# main.net
KiCad netlist of a schematic drawn in Altium Designer
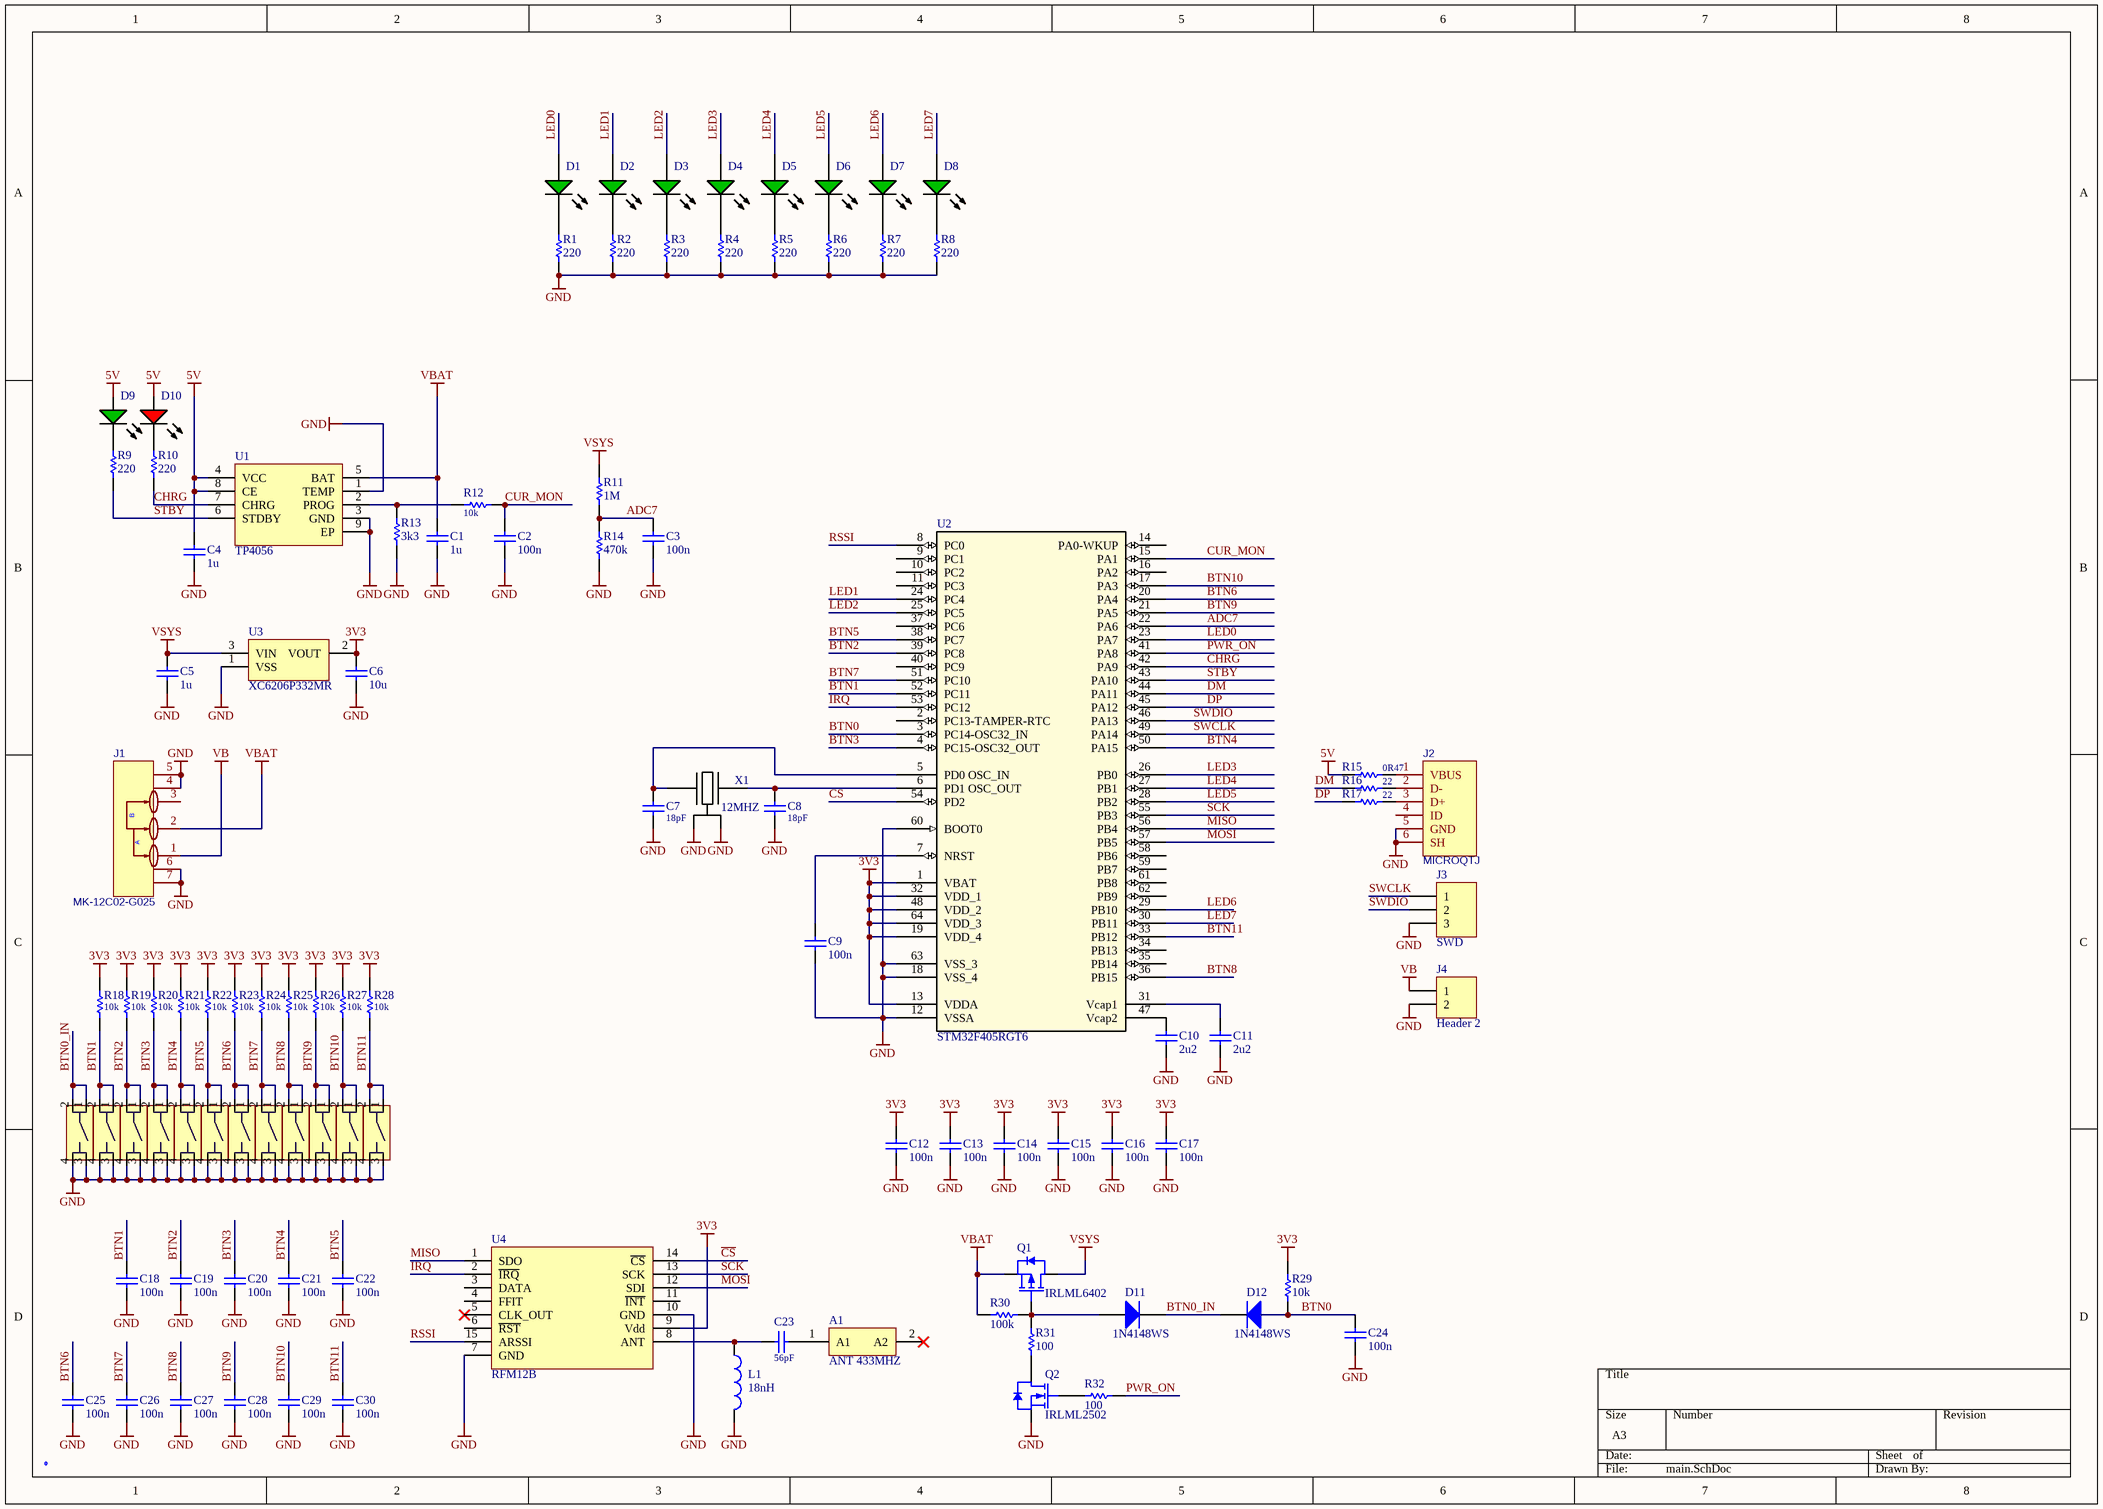
[diagram p0: main.SchDoc]

(export (version "E")
  (design (tool "Eeschema 10.0.6"))
  (components
    (comp (ref "A1")
      (value "ANT 433MHZ")
      (footprint "0433AT62A0020")
      (description "433 MHz ISM Antenna")
      (libsource (lib "Schlib1") (part "Component_2"))
    )
    (comp (ref "C1") (value "1u") (footprint "C1206") (libsource (lib "Miscellaneous Devices") (part "Cap")))
    (comp (ref "C2")
      (value "100n")
      (footprint "C0603")
      (libsource (lib "Miscellaneous Devices") (part "Cap"))
    )
    (comp (ref "C3")
      (value "100n")
      (footprint "C0603")
      (libsource (lib "Miscellaneous Devices") (part "Cap"))
    )
    (comp (ref "C4") (value "1u") (footprint "C1206") (libsource (lib "Miscellaneous Devices") (part "Cap")))
    (comp (ref "C5") (value "1u") (footprint "C1206") (libsource (lib "Miscellaneous Devices") (part "Cap")))
    (comp (ref "C6") (value "10u") (footprint "C1206") (libsource (lib "Miscellaneous Devices") (part "Cap")))
    (comp (ref "C7")
      (value "18pF")
      (footprint "C0402")
      (description "18pF 0402")
      (libsource (lib "Miscellaneous Devices") (part "CAP"))
    )
    (comp (ref "C8")
      (value "18pF")
      (footprint "C0402")
      (description "18pF 0402")
      (libsource (lib "Miscellaneous Devices") (part "CAP"))
    )
    (comp (ref "C9")
      (value "100n")
      (footprint "C0402")
      (libsource (lib "Miscellaneous Devices") (part "Cap"))
    )
    (comp (ref "C10")
      (value "2u2")
      (footprint "C0603")
      (libsource (lib "Miscellaneous Devices") (part "Cap"))
    )
    (comp (ref "C11")
      (value "2u2")
      (footprint "C0603")
      (libsource (lib "Miscellaneous Devices") (part "Cap"))
    )
    (comp (ref "C12")
      (value "100n")
      (footprint "C0402")
      (libsource (lib "Miscellaneous Devices") (part "Cap"))
    )
    (comp (ref "C13")
      (value "100n")
      (footprint "C0402")
      (libsource (lib "Miscellaneous Devices") (part "Cap"))
    )
    (comp (ref "C14")
      (value "100n")
      (footprint "C0402")
      (libsource (lib "Miscellaneous Devices") (part "Cap"))
    )
    (comp (ref "C15")
      (value "100n")
      (footprint "C0402")
      (libsource (lib "Miscellaneous Devices") (part "Cap"))
    )
    (comp (ref "C16")
      (value "100n")
      (footprint "C0402")
      (libsource (lib "Miscellaneous Devices") (part "Cap"))
    )
    (comp (ref "C17")
      (value "100n")
      (footprint "C0402")
      (libsource (lib "Miscellaneous Devices") (part "Cap"))
    )
    (comp (ref "C18")
      (value "100n")
      (footprint "C0402")
      (libsource (lib "Miscellaneous Devices") (part "Cap"))
    )
    (comp (ref "C19")
      (value "100n")
      (footprint "C0402")
      (libsource (lib "Miscellaneous Devices") (part "Cap"))
    )
    (comp (ref "C20")
      (value "100n")
      (footprint "C0402")
      (libsource (lib "Miscellaneous Devices") (part "Cap"))
    )
    (comp (ref "C21")
      (value "100n")
      (footprint "C0402")
      (libsource (lib "Miscellaneous Devices") (part "Cap"))
    )
    (comp (ref "C22")
      (value "100n")
      (footprint "C0402")
      (libsource (lib "Miscellaneous Devices") (part "Cap"))
    )
    (comp (ref "C23")
      (value "56pF")
      (footprint "C0402")
      (libsource (lib "Miscellaneous Devices") (part "CAP"))
    )
    (comp (ref "C24")
      (value "100n")
      (footprint "C0402")
      (libsource (lib "Miscellaneous Devices") (part "Cap"))
    )
    (comp (ref "C25")
      (value "100n")
      (footprint "C0402")
      (libsource (lib "Miscellaneous Devices") (part "Cap"))
    )
    (comp (ref "C26")
      (value "100n")
      (footprint "C0402")
      (libsource (lib "Miscellaneous Devices") (part "Cap"))
    )
    (comp (ref "C27")
      (value "100n")
      (footprint "C0402")
      (libsource (lib "Miscellaneous Devices") (part "Cap"))
    )
    (comp (ref "C28")
      (value "100n")
      (footprint "C0402")
      (libsource (lib "Miscellaneous Devices") (part "Cap"))
    )
    (comp (ref "C29")
      (value "100n")
      (footprint "C0402")
      (libsource (lib "Miscellaneous Devices") (part "Cap"))
    )
    (comp (ref "C30")
      (value "100n")
      (footprint "C0402")
      (libsource (lib "Miscellaneous Devices") (part "Cap"))
    )
    (comp (ref "D1")
      (value "GRN")
      (footprint "LED-0603-GRN")
      (description "LED 0603 GRN")
      (libsource (lib "Miscellaneous Devices") (part "LED-0603-GREEN"))
    )
    (comp (ref "D2")
      (value "GRN")
      (footprint "LED-0603-GRN")
      (description "LED 0603 GRN")
      (libsource (lib "Miscellaneous Devices") (part "LED-0603-GREEN"))
    )
    (comp (ref "D3")
      (value "GRN")
      (footprint "LED-0603-GRN")
      (description "LED 0603 GRN")
      (libsource (lib "Miscellaneous Devices") (part "LED-0603-GREEN"))
    )
    (comp (ref "D4")
      (value "GRN")
      (footprint "LED-0603-GRN")
      (description "LED 0603 GRN")
      (libsource (lib "Miscellaneous Devices") (part "LED-0603-GREEN"))
    )
    (comp (ref "D5")
      (value "GRN")
      (footprint "LED-0603-GRN")
      (description "LED 0603 GRN")
      (libsource (lib "Miscellaneous Devices") (part "LED-0603-GREEN"))
    )
    (comp (ref "D6")
      (value "GRN")
      (footprint "LED-0603-GRN")
      (description "LED 0603 GRN")
      (libsource (lib "Miscellaneous Devices") (part "LED-0603-GREEN"))
    )
    (comp (ref "D7")
      (value "GRN")
      (footprint "LED-0603-GRN")
      (description "LED 0603 GRN")
      (libsource (lib "Miscellaneous Devices") (part "LED-0603-GREEN"))
    )
    (comp (ref "D8")
      (value "GRN")
      (footprint "LED-0603-GRN")
      (description "LED 0603 GRN")
      (libsource (lib "Miscellaneous Devices") (part "LED-0603-GREEN"))
    )
    (comp (ref "D9")
      (value "GRN")
      (footprint "LED-0603-GRN")
      (description "LED 0603 GRN")
      (libsource (lib "") (part "LED-0603-GREEN_1"))
    )
    (comp (ref "D10")
      (value "RED")
      (footprint "LED-0603-RED")
      (description "LED 0603 RED")
      (libsource (lib "Miscellaneous Devices") (part "LED-0603-RED"))
    )
    (comp (ref "D11")
      (value "1N4148WS")
      (footprint "SOD-323")
      (libsource (lib "Miscellaneous Devices") (part "US1M-13-F"))
    )
    (comp (ref "D12")
      (value "1N4148WS")
      (footprint "SOD-323")
      (libsource (lib "Miscellaneous Devices") (part "US1M-13-F"))
    )
    (comp (ref "J1")
      (value "MK-12C02-G025")
      (footprint "SW-SMD_MK-12C02-G025")
      (fields (field (name "LCSC PART NUMBER") "C778186"))
      (libsource (lib "Schlib1") (part "MK-12C02-G025"))
    )
    (comp (ref "J2")
      (value "MICROQTJ")
      (footprint "CONN-USB-MICRO_#1")
      (libsource (lib "Schlib2") (part "MICROQTJ"))
    )
    (comp (ref "J3")
      (value "SWD")
      (footprint "HDR-1X3_2.54")
      (libsource (lib "Miscellaneous Devices") (part "Header 3"))
    )
    (comp (ref "J4")
      (value "Header 2")
      (footprint "HDR-1X2_2.54")
      (libsource (lib "Schlib1") (part "Header 2"))
    )
    (comp (ref "L1")
      (value "18nH")
      (footprint "L0402")
      (libsource (lib "Miscellaneous Devices") (part "BLM18AG601SN1D"))
    )
    (comp (ref "LOGO1") (value "LOGO") (footprint "LOGO") (libsource (lib "Schlib1") (part "LOGO")))
    (comp (ref "Q1") (value "IRLML6402") (footprint "SOT-23") (libsource (lib "") (part "2N7002_1")))
    (comp (ref "Q2")
      (value "IRLML2502")
      (footprint "SOT-23")
      (libsource (lib "Miscellaneous Devices") (part "2N7002"))
    )
    (comp (ref "R1")
      (value "220")
      (footprint "R0603")
      (libsource (lib "Miscellaneous Devices") (part "Res1"))
    )
    (comp (ref "R2")
      (value "220")
      (footprint "R0603")
      (libsource (lib "Miscellaneous Devices") (part "Res1"))
    )
    (comp (ref "R3")
      (value "220")
      (footprint "R0603")
      (libsource (lib "Miscellaneous Devices") (part "Res1"))
    )
    (comp (ref "R4")
      (value "220")
      (footprint "R0603")
      (libsource (lib "Miscellaneous Devices") (part "Res1"))
    )
    (comp (ref "R5")
      (value "220")
      (footprint "R0603")
      (libsource (lib "Miscellaneous Devices") (part "Res1"))
    )
    (comp (ref "R6")
      (value "220")
      (footprint "R0603")
      (libsource (lib "Miscellaneous Devices") (part "Res1"))
    )
    (comp (ref "R7")
      (value "220")
      (footprint "R0603")
      (libsource (lib "Miscellaneous Devices") (part "Res1"))
    )
    (comp (ref "R8")
      (value "220")
      (footprint "R0603")
      (libsource (lib "Miscellaneous Devices") (part "Res1"))
    )
    (comp (ref "R9")
      (value "220")
      (footprint "R0603")
      (libsource (lib "Miscellaneous Devices") (part "Res1"))
    )
    (comp (ref "R10")
      (value "220")
      (footprint "R0603")
      (libsource (lib "Miscellaneous Devices") (part "Res1"))
    )
    (comp (ref "R11")
      (value "1M")
      (footprint "R0603")
      (libsource (lib "Miscellaneous Devices") (part "Res1"))
    )
    (comp (ref "R12")
      (value "10k")
      (footprint "R0603")
      (libsource (lib "Miscellaneous Devices") (part "RES"))
    )
    (comp (ref "R13")
      (value "3k3")
      (footprint "R0603")
      (libsource (lib "Miscellaneous Devices") (part "Res1"))
    )
    (comp (ref "R14")
      (value "470k")
      (footprint "R0603")
      (libsource (lib "Miscellaneous Devices") (part "Res1"))
    )
    (comp (ref "R15")
      (value "0R47")
      (footprint "R0603")
      (libsource (lib "Miscellaneous Devices") (part "RES"))
    )
    (comp (ref "R16") (value "22") (footprint "R0603") (libsource (lib "Miscellaneous Devices") (part "RES")))
    (comp (ref "R17") (value "22") (footprint "R0603") (libsource (lib "Miscellaneous Devices") (part "RES")))
    (comp (ref "R18")
      (value "10k")
      (footprint "R0603")
      (libsource (lib "Miscellaneous Devices") (part "RES"))
    )
    (comp (ref "R19")
      (value "10k")
      (footprint "R0603")
      (libsource (lib "Miscellaneous Devices") (part "RES"))
    )
    (comp (ref "R20")
      (value "10k")
      (footprint "R0603")
      (libsource (lib "Miscellaneous Devices") (part "RES"))
    )
    (comp (ref "R21")
      (value "10k")
      (footprint "R0603")
      (libsource (lib "Miscellaneous Devices") (part "RES"))
    )
    (comp (ref "R22")
      (value "10k")
      (footprint "R0603")
      (libsource (lib "Miscellaneous Devices") (part "RES"))
    )
    (comp (ref "R23")
      (value "10k")
      (footprint "R0603")
      (libsource (lib "Miscellaneous Devices") (part "RES"))
    )
    (comp (ref "R24")
      (value "10k")
      (footprint "R0603")
      (libsource (lib "Miscellaneous Devices") (part "RES"))
    )
    (comp (ref "R25")
      (value "10k")
      (footprint "R0603")
      (libsource (lib "Miscellaneous Devices") (part "RES"))
    )
    (comp (ref "R26")
      (value "10k")
      (footprint "R0603")
      (libsource (lib "Miscellaneous Devices") (part "RES"))
    )
    (comp (ref "R27")
      (value "10k")
      (footprint "R0603")
      (libsource (lib "Miscellaneous Devices") (part "RES"))
    )
    (comp (ref "R28")
      (value "10k")
      (footprint "R0603")
      (libsource (lib "Miscellaneous Devices") (part "RES"))
    )
    (comp (ref "R29")
      (value "10k")
      (footprint "R0603")
      (libsource (lib "Miscellaneous Devices") (part "Res1"))
    )
    (comp (ref "R30")
      (value "100k")
      (footprint "R0603")
      (libsource (lib "Miscellaneous Devices") (part "Res1"))
    )
    (comp (ref "R31")
      (value "100")
      (footprint "R0603")
      (libsource (lib "Miscellaneous Devices") (part "Res1"))
    )
    (comp (ref "R32")
      (value "100")
      (footprint "R0603")
      (libsource (lib "Miscellaneous Devices") (part "Res1"))
    )
    (comp (ref "SW1")
      (value "PTS810SJS250")
      (footprint "BTN_PTS810")
      (libsource (lib "Miscellaneous Devices") (part "Component_1"))
    )
    (comp (ref "SW2")
      (value "PTS810SJS250")
      (footprint "BTN_PTS810")
      (libsource (lib "Miscellaneous Devices") (part "Component_1"))
    )
    (comp (ref "SW3")
      (value "PTS810SJS250")
      (footprint "BTN_PTS810")
      (libsource (lib "Miscellaneous Devices") (part "Component_1"))
    )
    (comp (ref "SW4")
      (value "PTS810SJS250")
      (footprint "BTN_PTS810")
      (libsource (lib "Miscellaneous Devices") (part "Component_1"))
    )
    (comp (ref "SW5")
      (value "PTS810SJS250")
      (footprint "BTN_PTS810")
      (libsource (lib "Miscellaneous Devices") (part "Component_1"))
    )
    (comp (ref "SW6")
      (value "PTS810SJS250")
      (footprint "BTN_PTS810")
      (libsource (lib "Miscellaneous Devices") (part "Component_1"))
    )
    (comp (ref "SW7")
      (value "PTS810SJS250")
      (footprint "BTN_PTS810")
      (libsource (lib "Miscellaneous Devices") (part "Component_1"))
    )
    (comp (ref "SW8")
      (value "PTS810SJS250")
      (footprint "BTN_PTS810")
      (libsource (lib "Miscellaneous Devices") (part "Component_1"))
    )
    (comp (ref "SW9")
      (value "PTS810SJS250")
      (footprint "BTN_PTS810")
      (libsource (lib "Miscellaneous Devices") (part "Component_1"))
    )
    (comp (ref "SW10")
      (value "PTS810SJS250")
      (footprint "BTN_PTS810")
      (libsource (lib "Miscellaneous Devices") (part "Component_1"))
    )
    (comp (ref "SW11")
      (value "PTS810SJS250")
      (footprint "BTN_PTS810")
      (libsource (lib "Miscellaneous Devices") (part "Component_1"))
    )
    (comp (ref "SW12")
      (value "PTS810SJS250")
      (footprint "BTN_PTS810")
      (libsource (lib "Miscellaneous Devices") (part "Component_1"))
    )
    (comp (ref "U1") (value "TP4056") (footprint "PowerSOIC-8") (libsource (lib "Schlib1") (part "TP4056")))
    (comp (ref "U2")
      (value "STM32F405RGT6")
      (footprint "LQFP-64")
      (description "MCU STM32F405RGT6")
      (libsource (lib "RozumLibrary") (part "STM32F405RGT6"))
    )
    (comp (ref "U3")
      (value "XC6206P332MR")
      (footprint "SOT-23")
      (libsource (lib "Schlib1") (part "Component_4_1"))
    )
    (comp (ref "U4") (value "RFM12B") (footprint "RFM12B") (libsource (lib "Schlib1") (part "Component_1_1")))
    (comp (ref "X1")
      (value "12MHZ")
      (footprint "CRYSTAL_3.2x2.5mm")
      (description "X322512MOB4SI")
      (libsource (lib "Miscellaneous Devices") (part "CRYSTAL 12MHZ 3.20mm x 2.50mm"))
    )
  )
  (nets
    (net (code "1") (name "/ADC7") (class "Default")
      (node (ref "C3") (pin "2") (pinfunction "2_2") (pintype "passive"))
      (node (ref "R11") (pin "1") (pinfunction "1_1") (pintype "passive"))
      (node (ref "R14") (pin "2") (pinfunction "2_2") (pintype "passive"))
      (node (ref "U2") (pin "22") (pinfunction "PA6_22") (pintype "bidirectional"))
    )
    (net (code "2") (name "/BTN0") (class "Default")
      (node (ref "C24") (pin "2") (pinfunction "2_2") (pintype "passive"))
      (node (ref "D12") (pin "1") (pinfunction "A_1") (pintype "passive"))
      (node (ref "R29") (pin "2") (pinfunction "2_2") (pintype "passive"))
      (node (ref "U2") (pin "3") (pinfunction "PC14-OSC32_IN_3") (pintype "bidirectional"))
    )
    (net (code "3") (name "/BTN0_IN") (class "Default")
      (node (ref "D11") (pin "2") (pinfunction "K_2") (pintype "passive"))
      (node (ref "D12") (pin "2") (pinfunction "K_2") (pintype "passive"))
      (node (ref "SW1") (pin "1") (pinfunction "1_1") (pintype "passive"))
      (node (ref "SW1") (pin "2") (pinfunction "2_2") (pintype "passive"))
    )
    (net (code "4") (name "/BTN1") (class "Default")
      (node (ref "C18") (pin "2") (pinfunction "2_2") (pintype "passive"))
      (node (ref "R18") (pin "1") (pinfunction "1_1") (pintype "passive"))
      (node (ref "SW2") (pin "1") (pinfunction "1_1") (pintype "passive"))
      (node (ref "SW2") (pin "2") (pinfunction "2_2") (pintype "passive"))
      (node (ref "U2") (pin "52") (pinfunction "PC11_52") (pintype "bidirectional"))
    )
    (net (code "5") (name "/BTN2") (class "Default")
      (node (ref "C19") (pin "2") (pinfunction "2_2") (pintype "passive"))
      (node (ref "R19") (pin "1") (pinfunction "1_1") (pintype "passive"))
      (node (ref "SW3") (pin "1") (pinfunction "1_1") (pintype "passive"))
      (node (ref "SW3") (pin "2") (pinfunction "2_2") (pintype "passive"))
      (node (ref "U2") (pin "39") (pinfunction "PC8_39") (pintype "bidirectional"))
    )
    (net (code "6") (name "/BTN3") (class "Default")
      (node (ref "C20") (pin "2") (pinfunction "2_2") (pintype "passive"))
      (node (ref "R20") (pin "1") (pinfunction "1_1") (pintype "passive"))
      (node (ref "SW4") (pin "1") (pinfunction "1_1") (pintype "passive"))
      (node (ref "SW4") (pin "2") (pinfunction "2_2") (pintype "passive"))
      (node (ref "U2") (pin "4") (pinfunction "PC15-OSC32_OUT_4") (pintype "bidirectional"))
    )
    (net (code "7") (name "/BTN4") (class "Default")
      (node (ref "C21") (pin "2") (pinfunction "2_2") (pintype "passive"))
      (node (ref "R21") (pin "1") (pinfunction "1_1") (pintype "passive"))
      (node (ref "SW5") (pin "1") (pinfunction "1_1") (pintype "passive"))
      (node (ref "SW5") (pin "2") (pinfunction "2_2") (pintype "passive"))
      (node (ref "U2") (pin "50") (pinfunction "PA15_50") (pintype "bidirectional"))
    )
    (net (code "8") (name "/BTN5") (class "Default")
      (node (ref "C22") (pin "2") (pinfunction "2_2") (pintype "passive"))
      (node (ref "R22") (pin "1") (pinfunction "1_1") (pintype "passive"))
      (node (ref "SW6") (pin "1") (pinfunction "1_1") (pintype "passive"))
      (node (ref "SW6") (pin "2") (pinfunction "2_2") (pintype "passive"))
      (node (ref "U2") (pin "38") (pinfunction "PC7_38") (pintype "bidirectional"))
    )
    (net (code "9") (name "/BTN6") (class "Default")
      (node (ref "C25") (pin "2") (pinfunction "2_2") (pintype "passive"))
      (node (ref "R23") (pin "1") (pinfunction "1_1") (pintype "passive"))
      (node (ref "SW7") (pin "1") (pinfunction "1_1") (pintype "passive"))
      (node (ref "SW7") (pin "2") (pinfunction "2_2") (pintype "passive"))
      (node (ref "U2") (pin "20") (pinfunction "PA4_20") (pintype "bidirectional"))
    )
    (net (code "10") (name "/BTN7") (class "Default")
      (node (ref "C26") (pin "2") (pinfunction "2_2") (pintype "passive"))
      (node (ref "R24") (pin "1") (pinfunction "1_1") (pintype "passive"))
      (node (ref "SW8") (pin "1") (pinfunction "1_1") (pintype "passive"))
      (node (ref "SW8") (pin "2") (pinfunction "2_2") (pintype "passive"))
      (node (ref "U2") (pin "51") (pinfunction "PC10_51") (pintype "bidirectional"))
    )
    (net (code "11") (name "/BTN8") (class "Default")
      (node (ref "C27") (pin "2") (pinfunction "2_2") (pintype "passive"))
      (node (ref "R25") (pin "1") (pinfunction "1_1") (pintype "passive"))
      (node (ref "SW9") (pin "1") (pinfunction "1_1") (pintype "passive"))
      (node (ref "SW9") (pin "2") (pinfunction "2_2") (pintype "passive"))
      (node (ref "U2") (pin "36") (pinfunction "PB15_36") (pintype "bidirectional"))
    )
    (net (code "12") (name "/BTN9") (class "Default")
      (node (ref "C28") (pin "2") (pinfunction "2_2") (pintype "passive"))
      (node (ref "R26") (pin "1") (pinfunction "1_1") (pintype "passive"))
      (node (ref "SW10") (pin "1") (pinfunction "1_1") (pintype "passive"))
      (node (ref "SW10") (pin "2") (pinfunction "2_2") (pintype "passive"))
      (node (ref "U2") (pin "21") (pinfunction "PA5_21") (pintype "bidirectional"))
    )
    (net (code "13") (name "/BTN10") (class "Default")
      (node (ref "C29") (pin "2") (pinfunction "2_2") (pintype "passive"))
      (node (ref "R27") (pin "1") (pinfunction "1_1") (pintype "passive"))
      (node (ref "SW11") (pin "1") (pinfunction "1_1") (pintype "passive"))
      (node (ref "SW11") (pin "2") (pinfunction "2_2") (pintype "passive"))
      (node (ref "U2") (pin "17") (pinfunction "PA3_17") (pintype "bidirectional"))
    )
    (net (code "14") (name "/BTN11") (class "Default")
      (node (ref "C30") (pin "2") (pinfunction "2_2") (pintype "passive"))
      (node (ref "R28") (pin "1") (pinfunction "1_1") (pintype "passive"))
      (node (ref "SW12") (pin "1") (pinfunction "1_1") (pintype "passive"))
      (node (ref "SW12") (pin "2") (pinfunction "2_2") (pintype "passive"))
      (node (ref "U2") (pin "33") (pinfunction "PB12_33") (pintype "bidirectional"))
    )
    (net (code "15") (name "/CHRG") (class "Default")
      (node (ref "R10") (pin "1") (pinfunction "1_1") (pintype "passive"))
      (node (ref "U1") (pin "7") (pinfunction "CHRG_7") (pintype "passive"))
      (node (ref "U2") (pin "42") (pinfunction "PA9_42") (pintype "bidirectional"))
    )
    (net (code "16") (name "/CUR_MON") (class "Default")
      (node (ref "C2") (pin "2") (pinfunction "2_2") (pintype "passive"))
      (node (ref "R12") (pin "1") (pinfunction "1_1") (pintype "passive"))
      (node (ref "U2") (pin "15") (pinfunction "PA1_15") (pintype "bidirectional"))
    )
    (net (code "17") (name "/DM") (class "Default")
      (node (ref "R16") (pin "2") (pinfunction "2_2") (pintype "passive"))
      (node (ref "U2") (pin "44") (pinfunction "PA11_44") (pintype "bidirectional"))
    )
    (net (code "18") (name "/DP") (class "Default")
      (node (ref "R17") (pin "2") (pinfunction "2_2") (pintype "passive"))
      (node (ref "U2") (pin "45") (pinfunction "PA12_45") (pintype "bidirectional"))
    )
    (net (code "19") (name "/LED0") (class "Default")
      (node (ref "D1") (pin "1") (pinfunction "A_1") (pintype "passive"))
      (node (ref "U2") (pin "23") (pinfunction "PA7_23") (pintype "bidirectional"))
    )
    (net (code "20") (name "/LED1") (class "Default")
      (node (ref "D2") (pin "1") (pinfunction "A_1") (pintype "passive"))
      (node (ref "U2") (pin "24") (pinfunction "PC4_24") (pintype "bidirectional"))
    )
    (net (code "21") (name "/LED2") (class "Default")
      (node (ref "D3") (pin "1") (pinfunction "A_1") (pintype "passive"))
      (node (ref "U2") (pin "25") (pinfunction "PC5_25") (pintype "bidirectional"))
    )
    (net (code "22") (name "/LED3") (class "Default")
      (node (ref "D4") (pin "1") (pinfunction "A_1") (pintype "passive"))
      (node (ref "U2") (pin "26") (pinfunction "PB0_26") (pintype "bidirectional"))
    )
    (net (code "23") (name "/LED4") (class "Default")
      (node (ref "D5") (pin "1") (pinfunction "A_1") (pintype "passive"))
      (node (ref "U2") (pin "27") (pinfunction "PB1_27") (pintype "bidirectional"))
    )
    (net (code "24") (name "/LED5") (class "Default")
      (node (ref "D6") (pin "1") (pinfunction "A_1") (pintype "passive"))
      (node (ref "U2") (pin "28") (pinfunction "PB2_28") (pintype "bidirectional"))
    )
    (net (code "25") (name "/LED6") (class "Default")
      (node (ref "D7") (pin "1") (pinfunction "A_1") (pintype "passive"))
      (node (ref "U2") (pin "29") (pinfunction "PB10_29") (pintype "bidirectional"))
    )
    (net (code "26") (name "/LED7") (class "Default")
      (node (ref "D8") (pin "1") (pinfunction "A_1") (pintype "passive"))
      (node (ref "U2") (pin "30") (pinfunction "PB11_30") (pintype "bidirectional"))
    )
    (net (code "27") (name "/MISO") (class "Default")
      (node (ref "U2") (pin "56") (pinfunction "PB4_56") (pintype "bidirectional"))
      (node (ref "U4") (pin "1") (pinfunction "SDO_1") (pintype "passive"))
    )
    (net (code "28") (name "/MOSI") (class "Default")
      (node (ref "U2") (pin "57") (pinfunction "PB5_57") (pintype "bidirectional"))
      (node (ref "U4") (pin "12") (pinfunction "SDI_12") (pintype "passive"))
    )
    (net (code "29") (name "/PWR_ON") (class "Default")
      (node (ref "R32") (pin "1") (pinfunction "1_1") (pintype "passive"))
      (node (ref "U2") (pin "41") (pinfunction "PA8_41") (pintype "bidirectional"))
    )
    (net (code "30") (name "/RSSI") (class "Default")
      (node (ref "U2") (pin "8") (pinfunction "PC0_8") (pintype "bidirectional"))
      (node (ref "U4") (pin "15") (pinfunction "ARSSI_15") (pintype "passive"))
    )
    (net (code "31") (name "/SCK") (class "Default")
      (node (ref "U2") (pin "55") (pinfunction "PB3_55") (pintype "bidirectional"))
      (node (ref "U4") (pin "13") (pinfunction "SCK_13") (pintype "passive"))
    )
    (net (code "32") (name "/STBY") (class "Default")
      (node (ref "R9") (pin "1") (pinfunction "1_1") (pintype "passive"))
      (node (ref "U1") (pin "6") (pinfunction "STDBY_6") (pintype "passive"))
      (node (ref "U2") (pin "43") (pinfunction "PA10_43") (pintype "bidirectional"))
    )
    (net (code "33") (name "/SWCLK") (class "Default")
      (node (ref "J3") (pin "1") (pinfunction "1_1") (pintype "passive"))
      (node (ref "U2") (pin "49") (pinfunction "PA14_49") (pintype "bidirectional"))
    )
    (net (code "34") (name "/SWDIO") (class "Default")
      (node (ref "J3") (pin "2") (pinfunction "2_2") (pintype "passive"))
      (node (ref "U2") (pin "46") (pinfunction "PA13_46") (pintype "bidirectional"))
    )
    (net (code "35") (name "/~{CS}") (class "Default")
      (node (ref "U2") (pin "54") (pinfunction "PD2_54") (pintype "bidirectional"))
      (node (ref "U4") (pin "14") (pinfunction "~{CS}_14") (pintype "passive"))
    )
    (net (code "36") (name "/~{IRQ}") (class "Default")
      (node (ref "U2") (pin "53") (pinfunction "PC12_53") (pintype "bidirectional"))
      (node (ref "U4") (pin "2") (pinfunction "~{IRQ}_2") (pintype "passive"))
    )
    (net (code "37") (name "3V3") (class "Default")
      (node (ref "C12") (pin "2") (pinfunction "2_2") (pintype "passive"))
      (node (ref "C13") (pin "2") (pinfunction "2_2") (pintype "passive"))
      (node (ref "C14") (pin "2") (pinfunction "2_2") (pintype "passive"))
      (node (ref "C15") (pin "2") (pinfunction "2_2") (pintype "passive"))
      (node (ref "C16") (pin "2") (pinfunction "2_2") (pintype "passive"))
      (node (ref "C17") (pin "2") (pinfunction "2_2") (pintype "passive"))
      (node (ref "C6") (pin "2") (pinfunction "2_2") (pintype "passive"))
      (node (ref "R18") (pin "2") (pinfunction "2_2") (pintype "passive"))
      (node (ref "R19") (pin "2") (pinfunction "2_2") (pintype "passive"))
      (node (ref "R20") (pin "2") (pinfunction "2_2") (pintype "passive"))
      (node (ref "R21") (pin "2") (pinfunction "2_2") (pintype "passive"))
      (node (ref "R22") (pin "2") (pinfunction "2_2") (pintype "passive"))
      (node (ref "R23") (pin "2") (pinfunction "2_2") (pintype "passive"))
      (node (ref "R24") (pin "2") (pinfunction "2_2") (pintype "passive"))
      (node (ref "R25") (pin "2") (pinfunction "2_2") (pintype "passive"))
      (node (ref "R26") (pin "2") (pinfunction "2_2") (pintype "passive"))
      (node (ref "R27") (pin "2") (pinfunction "2_2") (pintype "passive"))
      (node (ref "R28") (pin "2") (pinfunction "2_2") (pintype "passive"))
      (node (ref "R29") (pin "1") (pinfunction "1_1") (pintype "passive"))
      (node (ref "U2") (pin "1") (pinfunction "VBAT_1") (pintype "power_in"))
      (node (ref "U2") (pin "13") (pinfunction "VDDA_13") (pintype "power_in"))
      (node (ref "U2") (pin "19") (pinfunction "VDD_4_19") (pintype "power_in"))
      (node (ref "U2") (pin "32") (pinfunction "VDD_1_32") (pintype "power_in"))
      (node (ref "U2") (pin "48") (pinfunction "VDD_2_48") (pintype "power_in"))
      (node (ref "U2") (pin "64") (pinfunction "VDD_3_64") (pintype "power_in"))
      (node (ref "U3") (pin "2") (pinfunction "VOUT_2") (pintype "passive"))
      (node (ref "U4") (pin "9") (pinfunction "Vdd_9") (pintype "passive"))
    )
    (net (code "38") (name "5V") (class "Default")
      (node (ref "C4") (pin "2") (pinfunction "2_2") (pintype "passive"))
      (node (ref "D10") (pin "1") (pinfunction "A_1") (pintype "passive"))
      (node (ref "D9") (pin "1") (pinfunction "A_1") (pintype "passive"))
      (node (ref "R15") (pin "2") (pinfunction "2_2") (pintype "passive"))
      (node (ref "U1") (pin "4") (pinfunction "VCC_4") (pintype "passive"))
      (node (ref "U1") (pin "8") (pinfunction "CE_8") (pintype "passive"))
    )
    (net (code "39") (name "GND") (class "Default")
      (node (ref "C1") (pin "1") (pinfunction "1_1") (pintype "passive"))
      (node (ref "C10") (pin "1") (pinfunction "1_1") (pintype "passive"))
      (node (ref "C11") (pin "1") (pinfunction "1_1") (pintype "passive"))
      (node (ref "C12") (pin "1") (pinfunction "1_1") (pintype "passive"))
      (node (ref "C13") (pin "1") (pinfunction "1_1") (pintype "passive"))
      (node (ref "C14") (pin "1") (pinfunction "1_1") (pintype "passive"))
      (node (ref "C15") (pin "1") (pinfunction "1_1") (pintype "passive"))
      (node (ref "C16") (pin "1") (pinfunction "1_1") (pintype "passive"))
      (node (ref "C17") (pin "1") (pinfunction "1_1") (pintype "passive"))
      (node (ref "C18") (pin "1") (pinfunction "1_1") (pintype "passive"))
      (node (ref "C19") (pin "1") (pinfunction "1_1") (pintype "passive"))
      (node (ref "C2") (pin "1") (pinfunction "1_1") (pintype "passive"))
      (node (ref "C20") (pin "1") (pinfunction "1_1") (pintype "passive"))
      (node (ref "C21") (pin "1") (pinfunction "1_1") (pintype "passive"))
      (node (ref "C22") (pin "1") (pinfunction "1_1") (pintype "passive"))
      (node (ref "C24") (pin "1") (pinfunction "1_1") (pintype "passive"))
      (node (ref "C25") (pin "1") (pinfunction "1_1") (pintype "passive"))
      (node (ref "C26") (pin "1") (pinfunction "1_1") (pintype "passive"))
      (node (ref "C27") (pin "1") (pinfunction "1_1") (pintype "passive"))
      (node (ref "C28") (pin "1") (pinfunction "1_1") (pintype "passive"))
      (node (ref "C29") (pin "1") (pinfunction "1_1") (pintype "passive"))
      (node (ref "C3") (pin "1") (pinfunction "1_1") (pintype "passive"))
      (node (ref "C30") (pin "1") (pinfunction "1_1") (pintype "passive"))
      (node (ref "C4") (pin "1") (pinfunction "1_1") (pintype "passive"))
      (node (ref "C5") (pin "1") (pinfunction "1_1") (pintype "passive"))
      (node (ref "C6") (pin "1") (pinfunction "1_1") (pintype "passive"))
      (node (ref "C7") (pin "1") (pinfunction "1_1") (pintype "passive"))
      (node (ref "C8") (pin "1") (pinfunction "1_1") (pintype "passive"))
      (node (ref "C9") (pin "1") (pinfunction "1_1") (pintype "passive"))
      (node (ref "J1") (pin "4") (pinfunction "4_4") (pintype "passive"))
      (node (ref "J1") (pin "5") (pinfunction "5_5") (pintype "passive"))
      (node (ref "J1") (pin "6") (pinfunction "6_6") (pintype "passive"))
      (node (ref "J1") (pin "7") (pinfunction "7_7") (pintype "passive"))
      (node (ref "J2") (pin "5") (pinfunction "GND_5") (pintype "passive"))
      (node (ref "J2") (pin "6") (pinfunction "SH_6") (pintype "passive"))
      (node (ref "J3") (pin "3") (pinfunction "3_3") (pintype "passive"))
      (node (ref "J4") (pin "2") (pinfunction "2_2") (pintype "passive"))
      (node (ref "L1") (pin "2") (pinfunction "2_2") (pintype "passive"))
      (node (ref "Q2") (pin "2") (pinfunction "SOURCE_2") (pintype "passive"))
      (node (ref "R1") (pin "1") (pinfunction "1_1") (pintype "passive"))
      (node (ref "R13") (pin "1") (pinfunction "1_1") (pintype "passive"))
      (node (ref "R14") (pin "1") (pinfunction "1_1") (pintype "passive"))
      (node (ref "R2") (pin "1") (pinfunction "1_1") (pintype "passive"))
      (node (ref "R3") (pin "1") (pinfunction "1_1") (pintype "passive"))
      (node (ref "R4") (pin "1") (pinfunction "1_1") (pintype "passive"))
      (node (ref "R5") (pin "1") (pinfunction "1_1") (pintype "passive"))
      (node (ref "R6") (pin "1") (pinfunction "1_1") (pintype "passive"))
      (node (ref "R7") (pin "1") (pinfunction "1_1") (pintype "passive"))
      (node (ref "R8") (pin "1") (pinfunction "1_1") (pintype "passive"))
      (node (ref "SW1") (pin "3") (pinfunction "3_3") (pintype "passive"))
      (node (ref "SW1") (pin "4") (pinfunction "4_4") (pintype "passive"))
      (node (ref "SW10") (pin "3") (pinfunction "3_3") (pintype "passive"))
      (node (ref "SW10") (pin "4") (pinfunction "4_4") (pintype "passive"))
      (node (ref "SW11") (pin "3") (pinfunction "3_3") (pintype "passive"))
      (node (ref "SW11") (pin "4") (pinfunction "4_4") (pintype "passive"))
      (node (ref "SW12") (pin "3") (pinfunction "3_3") (pintype "passive"))
      (node (ref "SW12") (pin "4") (pinfunction "4_4") (pintype "passive"))
      (node (ref "SW2") (pin "3") (pinfunction "3_3") (pintype "passive"))
      (node (ref "SW2") (pin "4") (pinfunction "4_4") (pintype "passive"))
      (node (ref "SW3") (pin "3") (pinfunction "3_3") (pintype "passive"))
      (node (ref "SW3") (pin "4") (pinfunction "4_4") (pintype "passive"))
      (node (ref "SW4") (pin "3") (pinfunction "3_3") (pintype "passive"))
      (node (ref "SW4") (pin "4") (pinfunction "4_4") (pintype "passive"))
      (node (ref "SW5") (pin "3") (pinfunction "3_3") (pintype "passive"))
      (node (ref "SW5") (pin "4") (pinfunction "4_4") (pintype "passive"))
      (node (ref "SW6") (pin "3") (pinfunction "3_3") (pintype "passive"))
      (node (ref "SW6") (pin "4") (pinfunction "4_4") (pintype "passive"))
      (node (ref "SW7") (pin "3") (pinfunction "3_3") (pintype "passive"))
      (node (ref "SW7") (pin "4") (pinfunction "4_4") (pintype "passive"))
      (node (ref "SW8") (pin "3") (pinfunction "3_3") (pintype "passive"))
      (node (ref "SW8") (pin "4") (pinfunction "4_4") (pintype "passive"))
      (node (ref "SW9") (pin "3") (pinfunction "3_3") (pintype "passive"))
      (node (ref "SW9") (pin "4") (pinfunction "4_4") (pintype "passive"))
      (node (ref "U1") (pin "1") (pinfunction "TEMP_1") (pintype "passive"))
      (node (ref "U1") (pin "3") (pinfunction "GND_3") (pintype "passive"))
      (node (ref "U1") (pin "9") (pinfunction "EP_9") (pintype "passive"))
      (node (ref "U2") (pin "12") (pinfunction "VSSA_12") (pintype "power_in"))
      (node (ref "U2") (pin "18") (pinfunction "VSS_4_18") (pintype "power_in"))
      (node (ref "U2") (pin "60") (pinfunction "BOOT0_60") (pintype "input"))
      (node (ref "U2") (pin "63") (pinfunction "VSS_3_63") (pintype "power_in"))
      (node (ref "U3") (pin "1") (pinfunction "VSS_1") (pintype "passive"))
      (node (ref "U4") (pin "10") (pinfunction "GND_10") (pintype "passive"))
      (node (ref "U4") (pin "7") (pinfunction "GND_7") (pintype "passive"))
      (node (ref "X1") (pin "2") (pinfunction "GND_2") (pintype "passive"))
      (node (ref "X1") (pin "4") (pinfunction "GND_4") (pintype "passive"))
    )
    (net (code "40") (name "Net-(A1-A1)") (class "Default")
      (node (ref "A1") (pin "1") (pinfunction "A1_1") (pintype "passive"))
      (node (ref "C23") (pin "1") (pinfunction "1_1") (pintype "passive"))
    )
    (net (code "41") (name "Net-(D1-K)") (class "Default")
      (node (ref "D1") (pin "2") (pinfunction "K_2") (pintype "passive"))
      (node (ref "R1") (pin "2") (pinfunction "2_2") (pintype "passive"))
    )
    (net (code "42") (name "Net-(D2-K)") (class "Default")
      (node (ref "D2") (pin "2") (pinfunction "K_2") (pintype "passive"))
      (node (ref "R2") (pin "2") (pinfunction "2_2") (pintype "passive"))
    )
    (net (code "43") (name "Net-(D3-K)") (class "Default")
      (node (ref "D3") (pin "2") (pinfunction "K_2") (pintype "passive"))
      (node (ref "R3") (pin "2") (pinfunction "2_2") (pintype "passive"))
    )
    (net (code "44") (name "Net-(D4-K)") (class "Default")
      (node (ref "D4") (pin "2") (pinfunction "K_2") (pintype "passive"))
      (node (ref "R4") (pin "2") (pinfunction "2_2") (pintype "passive"))
    )
    (net (code "45") (name "Net-(D5-K)") (class "Default")
      (node (ref "D5") (pin "2") (pinfunction "K_2") (pintype "passive"))
      (node (ref "R5") (pin "2") (pinfunction "2_2") (pintype "passive"))
    )
    (net (code "46") (name "Net-(D6-K)") (class "Default")
      (node (ref "D6") (pin "2") (pinfunction "K_2") (pintype "passive"))
      (node (ref "R6") (pin "2") (pinfunction "2_2") (pintype "passive"))
    )
    (net (code "47") (name "Net-(D7-K)") (class "Default")
      (node (ref "D7") (pin "2") (pinfunction "K_2") (pintype "passive"))
      (node (ref "R7") (pin "2") (pinfunction "2_2") (pintype "passive"))
    )
    (net (code "48") (name "Net-(D8-K)") (class "Default")
      (node (ref "D8") (pin "2") (pinfunction "K_2") (pintype "passive"))
      (node (ref "R8") (pin "2") (pinfunction "2_2") (pintype "passive"))
    )
    (net (code "49") (name "Net-(D9-K)") (class "Default")
      (node (ref "D9") (pin "2") (pinfunction "K_2") (pintype "passive"))
      (node (ref "R9") (pin "2") (pinfunction "2_2") (pintype "passive"))
    )
    (net (code "50") (name "Net-(D10-K)") (class "Default")
      (node (ref "D10") (pin "2") (pinfunction "K_2") (pintype "passive"))
      (node (ref "R10") (pin "2") (pinfunction "2_2") (pintype "passive"))
    )
    (net (code "51") (name "Net-(D11-A)") (class "Default")
      (node (ref "D11") (pin "1") (pinfunction "A_1") (pintype "passive"))
      (node (ref "Q1") (pin "1") (pinfunction "GATE_1") (pintype "passive"))
      (node (ref "R30") (pin "1") (pinfunction "1_1") (pintype "passive"))
      (node (ref "R31") (pin "2") (pinfunction "2_2") (pintype "passive"))
    )
    (net (code "52") (name "Net-(J2-D+)") (class "Default")
      (node (ref "J2") (pin "3") (pinfunction "D+_3") (pintype "passive"))
      (node (ref "R17") (pin "1") (pinfunction "1_1") (pintype "passive"))
    )
    (net (code "53") (name "Net-(J2-D-)") (class "Default")
      (node (ref "J2") (pin "2") (pinfunction "D-_2") (pintype "passive"))
      (node (ref "R16") (pin "1") (pinfunction "1_1") (pintype "passive"))
    )
    (net (code "54") (name "Net-(J2-VBUS)") (class "Default")
      (node (ref "J2") (pin "1") (pinfunction "VBUS_1") (pintype "passive"))
      (node (ref "R15") (pin "1") (pinfunction "1_1") (pintype "passive"))
    )
    (net (code "55") (name "Net-(Q2-DRAIN)") (class "Default")
      (node (ref "Q2") (pin "3") (pinfunction "DRAIN_3") (pintype "passive"))
      (node (ref "R31") (pin "1") (pinfunction "1_1") (pintype "passive"))
    )
    (net (code "56") (name "Net-(Q2-GATE)") (class "Default")
      (node (ref "Q2") (pin "1") (pinfunction "GATE_1") (pintype "passive"))
      (node (ref "R32") (pin "2") (pinfunction "2_2") (pintype "passive"))
    )
    (net (code "57") (name "Net-(U1-PROG)") (class "Default")
      (node (ref "R12") (pin "2") (pinfunction "2_2") (pintype "passive"))
      (node (ref "R13") (pin "2") (pinfunction "2_2") (pintype "passive"))
      (node (ref "U1") (pin "2") (pinfunction "PROG_2") (pintype "passive"))
    )
    (net (code "58") (name "Net-(U2-NRST)") (class "Default")
      (node (ref "C9") (pin "2") (pinfunction "2_2") (pintype "passive"))
      (node (ref "U2") (pin "7") (pinfunction "NRST_7") (pintype "bidirectional"))
    )
    (net (code "59") (name "Net-(U2-PD0_OSC_IN)") (class "Default")
      (node (ref "C7") (pin "2") (pinfunction "2_2") (pintype "passive"))
      (node (ref "U2") (pin "5") (pinfunction "PD0_OSC_IN_5") (pintype "passive"))
      (node (ref "X1") (pin "1") (pinfunction "X1_1") (pintype "passive"))
    )
    (net (code "60") (name "Net-(U2-PD1_OSC_OUT)") (class "Default")
      (node (ref "C8") (pin "2") (pinfunction "2_2") (pintype "passive"))
      (node (ref "U2") (pin "6") (pinfunction "PD1_OSC_OUT_6") (pintype "passive"))
      (node (ref "X1") (pin "3") (pinfunction "X2_3") (pintype "passive"))
    )
    (net (code "61") (name "Net-(U2-Vcap1)") (class "Default")
      (node (ref "C11") (pin "2") (pinfunction "2_2") (pintype "passive"))
      (node (ref "U2") (pin "31") (pinfunction "Vcap1_31") (pintype "power_in"))
    )
    (net (code "62") (name "Net-(U2-Vcap2)") (class "Default")
      (node (ref "C10") (pin "2") (pinfunction "2_2") (pintype "passive"))
      (node (ref "U2") (pin "47") (pinfunction "Vcap2_47") (pintype "power_in"))
    )
    (net (code "63") (name "Net-(U4-ANT)") (class "Default")
      (node (ref "C23") (pin "2") (pinfunction "2_2") (pintype "passive"))
      (node (ref "L1") (pin "1") (pinfunction "1_1") (pintype "passive"))
      (node (ref "U4") (pin "8") (pinfunction "ANT_8") (pintype "passive"))
    )
    (net (code "64") (name "VB") (class "Default")
      (node (ref "J1") (pin "1") (pinfunction "1_1") (pintype "passive"))
      (node (ref "J4") (pin "1") (pinfunction "1_1") (pintype "passive"))
    )
    (net (code "65") (name "VBAT") (class "Default")
      (node (ref "C1") (pin "2") (pinfunction "2_2") (pintype "passive"))
      (node (ref "J1") (pin "2") (pinfunction "2_2") (pintype "passive"))
      (node (ref "Q1") (pin "2") (pinfunction "SOURCE_2") (pintype "passive"))
      (node (ref "R30") (pin "2") (pinfunction "2_2") (pintype "passive"))
      (node (ref "U1") (pin "5") (pinfunction "BAT_5") (pintype "passive"))
    )
    (net (code "66") (name "VSYS") (class "Default")
      (node (ref "C5") (pin "2") (pinfunction "2_2") (pintype "passive"))
      (node (ref "Q1") (pin "3") (pinfunction "DRAIN_3") (pintype "passive"))
      (node (ref "R11") (pin "2") (pinfunction "2_2") (pintype "passive"))
      (node (ref "U3") (pin "3") (pinfunction "VIN_3") (pintype "passive"))
    )
    (net (code "67") (name "unconnected-(A1-A2-Pad2)") (class "Default")
      (node (ref "A1") (pin "2") (pinfunction "A2_2") (pintype "passive+no_connect"))
    )
    (net (code "68") (name "unconnected-(J1-Pad3)") (class "Default")
      (node (ref "J1") (pin "3") (pinfunction "3_3") (pintype "passive"))
    )
    (net (code "69") (name "unconnected-(J2-ID-Pad4)") (class "Default")
      (node (ref "J2") (pin "4") (pinfunction "ID_4") (pintype "passive"))
    )
    (net (code "70") (name "unconnected-(U2-PA0-WKUP-Pad14)") (class "Default")
      (node (ref "U2") (pin "14") (pinfunction "PA0-WKUP_14") (pintype "bidirectional"))
    )
    (net (code "71") (name "unconnected-(U2-PA2-Pad16)") (class "Default")
      (node (ref "U2") (pin "16") (pinfunction "PA2_16") (pintype "bidirectional"))
    )
    (net (code "72") (name "unconnected-(U2-PB6-Pad58)") (class "Default")
      (node (ref "U2") (pin "58") (pinfunction "PB6_58") (pintype "bidirectional"))
    )
    (net (code "73") (name "unconnected-(U2-PB7-Pad59)") (class "Default")
      (node (ref "U2") (pin "59") (pinfunction "PB7_59") (pintype "bidirectional"))
    )
    (net (code "74") (name "unconnected-(U2-PB8-Pad61)") (class "Default")
      (node (ref "U2") (pin "61") (pinfunction "PB8_61") (pintype "bidirectional"))
    )
    (net (code "75") (name "unconnected-(U2-PB9-Pad62)") (class "Default")
      (node (ref "U2") (pin "62") (pinfunction "PB9_62") (pintype "bidirectional"))
    )
    (net (code "76") (name "unconnected-(U2-PB13-Pad34)") (class "Default")
      (node (ref "U2") (pin "34") (pinfunction "PB13_34") (pintype "bidirectional"))
    )
    (net (code "77") (name "unconnected-(U2-PB14-Pad35)") (class "Default")
      (node (ref "U2") (pin "35") (pinfunction "PB14_35") (pintype "bidirectional"))
    )
    (net (code "78") (name "unconnected-(U2-PC1-Pad9)") (class "Default")
      (node (ref "U2") (pin "9") (pinfunction "PC1_9") (pintype "bidirectional"))
    )
    (net (code "79") (name "unconnected-(U2-PC2-Pad10)") (class "Default")
      (node (ref "U2") (pin "10") (pinfunction "PC2_10") (pintype "bidirectional"))
    )
    (net (code "80") (name "unconnected-(U2-PC3-Pad11)") (class "Default")
      (node (ref "U2") (pin "11") (pinfunction "PC3_11") (pintype "bidirectional"))
    )
    (net (code "81") (name "unconnected-(U2-PC6-Pad37)") (class "Default")
      (node (ref "U2") (pin "37") (pinfunction "PC6_37") (pintype "bidirectional"))
    )
    (net (code "82") (name "unconnected-(U2-PC9-Pad40)") (class "Default")
      (node (ref "U2") (pin "40") (pinfunction "PC9_40") (pintype "bidirectional"))
    )
    (net (code "83") (name "unconnected-(U2-PC13-TAMPER-RTC-Pad2)") (class "Default")
      (node (ref "U2") (pin "2") (pinfunction "PC13-TAMPER-RTC_2") (pintype "bidirectional"))
    )
    (net (code "84") (name "unconnected-(U4-CLK_OUT-Pad5)") (class "Default")
      (node (ref "U4") (pin "5") (pinfunction "CLK_OUT_5") (pintype "passive+no_connect"))
    )
    (net (code "85") (name "unconnected-(U4-DATA-Pad3)") (class "Default")
      (node (ref "U4") (pin "3") (pinfunction "DATA_3") (pintype "passive"))
    )
    (net (code "86") (name "unconnected-(U4-FFIT-Pad4)") (class "Default")
      (node (ref "U4") (pin "4") (pinfunction "FFIT_4") (pintype "passive"))
    )
    (net (code "87") (name "unconnected-(U4-~{INT}-Pad11)") (class "Default")
      (node (ref "U4") (pin "11") (pinfunction "~{INT}_11") (pintype "passive"))
    )
    (net (code "88") (name "unconnected-(U4-~{RST}-Pad6)") (class "Default")
      (node (ref "U4") (pin "6") (pinfunction "~{RST}_6") (pintype "passive"))
    )
  )
)
